# ultra-violet-tooth-sensor-mk-3_0.net
KiCad netlist of a schematic drawn in EAGLE
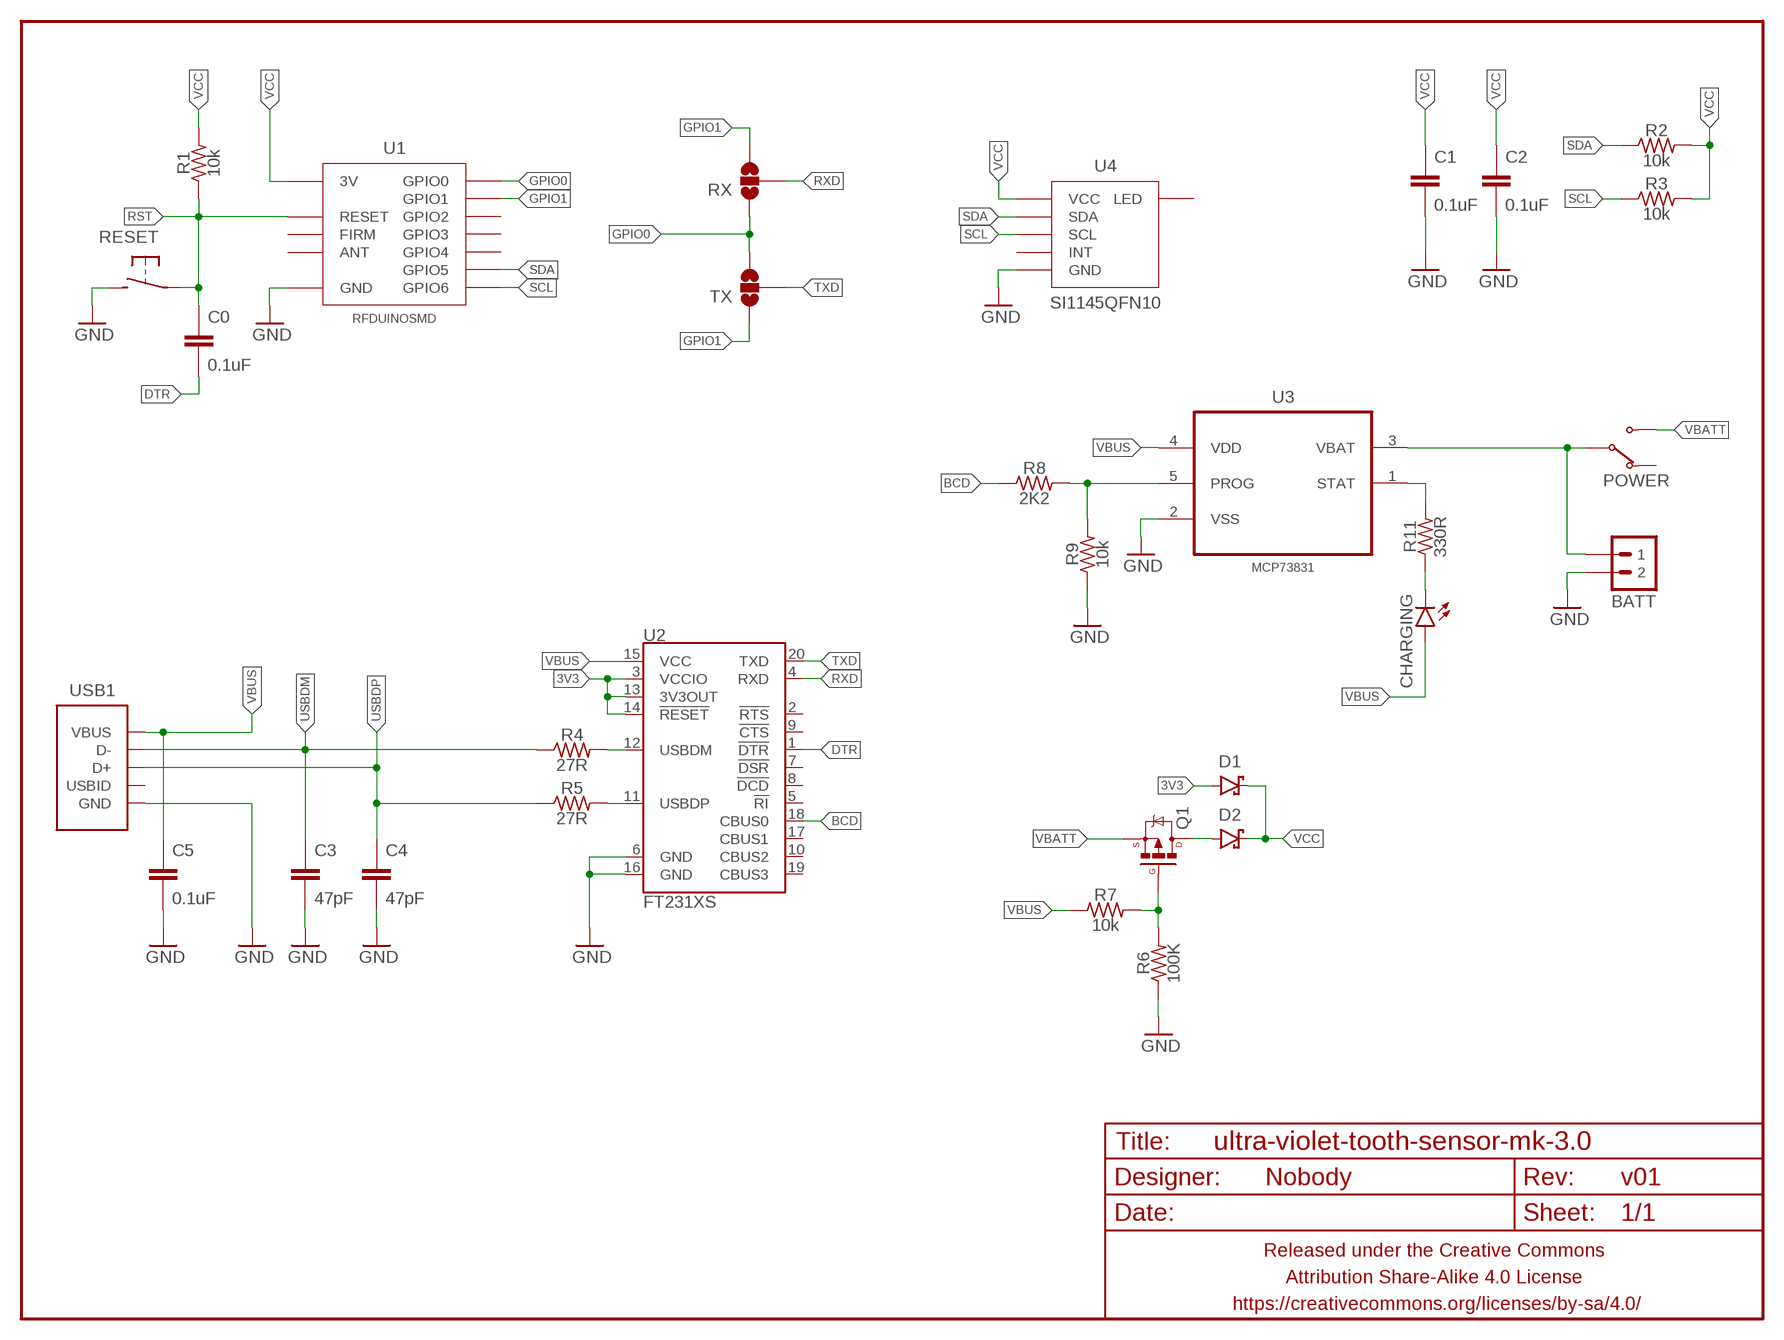
[diagram p0: schematic, sheet 1]

(export (version "E")
  (design (tool "Eeschema 10.0.6"))
  (components
    (comp (ref "BATT")
      (value "M02JST-2MM-SMT")
      (footprint "eagle-import:JST-2-SMD")
      (libsource (lib "eagle-import") (part "M02JST-2MM-SMT"))
    )
    (comp (ref "C0")
      (value "0.1uF")
      (footprint "eagle-import:C0603")
      (libsource (lib "eagle-import") (part "CAPACITOR-CERAMICC0603"))
    )
    (comp (ref "C1")
      (value "0.1uF")
      (footprint "eagle-import:C0603")
      (libsource (lib "eagle-import") (part "CAPACITOR-CERAMICC0603"))
    )
    (comp (ref "C2")
      (value "0.1uF")
      (footprint "eagle-import:C0603")
      (libsource (lib "eagle-import") (part "CAPACITOR-CERAMICC0603"))
    )
    (comp (ref "C3")
      (value "47pF")
      (footprint "eagle-import:C0603")
      (libsource (lib "eagle-import") (part "CAPACITOR-CERAMICC0603"))
    )
    (comp (ref "C4")
      (value "47pF")
      (footprint "eagle-import:C0603")
      (libsource (lib "eagle-import") (part "CAPACITOR-CERAMICC0603"))
    )
    (comp (ref "C5")
      (value "0.1uF")
      (footprint "eagle-import:C0603")
      (libsource (lib "eagle-import") (part "CAPACITOR-CERAMICC0603"))
    )
    (comp (ref "CHARGING")
      (value "LED1206")
      (footprint "eagle-import:LED-1206")
      (libsource (lib "eagle-import") (part "LED1206"))
    )
    (comp (ref "D1")
      (value "DIODE-SCHOTTKYSMA")
      (footprint "eagle-import:SMA-DIODE-SCHOTTKY")
      (libsource (lib "eagle-import") (part "DIODE-SCHOTTKYSMA"))
    )
    (comp (ref "D2")
      (value "DIODE-SCHOTTKYSMA")
      (footprint "eagle-import:SMA-DIODE-SCHOTTKY")
      (libsource (lib "eagle-import") (part "DIODE-SCHOTTKYSMA"))
    )
    (comp (ref "FRAME1")
      (value "FRAME-LETTERNO_PACKAGE")
      (footprint "eagle-import:DUMMY")
      (fields (field (name "DESIGNER") "Nobody"))
      (libsource (lib "eagle-import") (part "FRAME-LETTERNO_PACKAGE"))
    )
    (comp (ref "POWER")
      (value "SWITCH-SPDTPTH-RA-2.54MM")
      (footprint "eagle-import:SPDT-RA-2.54MM")
      (libsource (lib "eagle-import") (part "SWITCH-SPDTPTH-RA-2.54MM"))
    )
    (comp (ref "Q1")
      (value "MOSFET-PCHANNELIRLML2244")
      (footprint "eagle-import:SOT23-3")
      (libsource (lib "eagle-import") (part "MOSFET-PCHANNELIRLML2244"))
    )
    (comp (ref "R1")
      (value "10k")
      (footprint "eagle-import:R0603")
      (libsource (lib "eagle-import") (part "RESISTORR0603"))
    )
    (comp (ref "R2")
      (value "10k")
      (footprint "eagle-import:R0603")
      (libsource (lib "eagle-import") (part "RESISTORR0603"))
    )
    (comp (ref "R3")
      (value "10k")
      (footprint "eagle-import:R0603")
      (libsource (lib "eagle-import") (part "RESISTORR0603"))
    )
    (comp (ref "R4")
      (value "27R")
      (footprint "eagle-import:R0603")
      (libsource (lib "eagle-import") (part "RESISTORR0603"))
    )
    (comp (ref "R5")
      (value "27R")
      (footprint "eagle-import:R0603")
      (libsource (lib "eagle-import") (part "RESISTORR0603"))
    )
    (comp (ref "R6")
      (value "100K")
      (footprint "eagle-import:R0603")
      (libsource (lib "eagle-import") (part "RESISTORR0603"))
    )
    (comp (ref "R7")
      (value "10k")
      (footprint "eagle-import:R0603")
      (libsource (lib "eagle-import") (part "RESISTORR0603"))
    )
    (comp (ref "R8")
      (value "2K2")
      (footprint "eagle-import:R0603")
      (libsource (lib "eagle-import") (part "RESISTORR0603"))
    )
    (comp (ref "R9")
      (value "10k")
      (footprint "eagle-import:R0603")
      (libsource (lib "eagle-import") (part "RESISTORR0603"))
    )
    (comp (ref "R11")
      (value "330R")
      (footprint "eagle-import:R0603")
      (libsource (lib "eagle-import") (part "RESISTORR0603"))
    )
    (comp (ref "RESET")
      (value "SPST-NO-TACT3MM-RA")
      (footprint "eagle-import:TACTILE-PTH-SIDE")
      (libsource (lib "eagle-import") (part "SPST-NO-TACT3MM-RA"))
    )
    (comp (ref "RX")
      (value "JUMPER-PAD-3-NOFULL_BOX_SILK")
      (footprint "eagle-import:PAD-JUMPER-3-NO_YES_SILK_FULL_BOX")
      (libsource (lib "eagle-import") (part "JUMPER-PAD-3-NOFULL_BOX_SILK"))
    )
    (comp (ref "TX")
      (value "JUMPER-PAD-3-NOFULL_BOX_SILK")
      (footprint "eagle-import:PAD-JUMPER-3-NO_YES_SILK_FULL_BOX")
      (libsource (lib "eagle-import") (part "JUMPER-PAD-3-NOFULL_BOX_SILK"))
    )
    (comp (ref "U1")
      (value "RFDUINOSMD")
      (footprint "eagle-import:RFDUINO-SMD")
      (libsource (lib "eagle-import") (part "RFDUINOSMD"))
    )
    (comp (ref "U2")
      (value "FT231XS")
      (footprint "eagle-import:SSOP20_L")
      (libsource (lib "eagle-import") (part "FT231XS"))
    )
    (comp (ref "U3")
      (value "MCP73831")
      (footprint "eagle-import:SOT95P280X145-5N")
      (fields (field (name "MPN") "MCP73831T-2ACI/OT"))
      (libsource (lib "eagle-import") (part "MCP73831T-2ACI/OT"))
    )
    (comp (ref "U4")
      (value "SI1145QFN10")
      (footprint "eagle-import:SI1145")
      (libsource (lib "eagle-import") (part "SI1145QFN10"))
    )
    (comp (ref "USB1")
      (value "USB-ABCOMBO")
      (footprint "eagle-import:USB-MICRO-B-FCI-CUTOUT")
      (libsource (lib "eagle-import") (part "USB-ABCOMBO"))
    )
  )
  (nets
    (net (code "1") (name "3V3") (class "Default")
      (node (ref "D1") (pin "A") (pinfunction "A_A") (pintype "passive"))
      (node (ref "U2") (pin "13") (pinfunction "3V3OUT_13") (pintype "bidirectional"))
      (node (ref "U2") (pin "14") (pinfunction "~{RESET}_14") (pintype "bidirectional"))
      (node (ref "U2") (pin "3") (pinfunction "VCCIO_3") (pintype "bidirectional"))
    )
    (net (code "2") (name "BCD") (class "Default")
      (node (ref "R8") (pin "1") (pinfunction "1_1") (pintype "passive"))
      (node (ref "U2") (pin "18") (pinfunction "CBUS0_18") (pintype "bidirectional"))
    )
    (net (code "3") (name "DTR") (class "Default")
      (node (ref "C0") (pin "2") (pinfunction "2_2") (pintype "passive"))
      (node (ref "U2") (pin "1") (pinfunction "~{DTR}_1") (pintype "bidirectional"))
    )
    (net (code "4") (name "GND") (class "Default")
      (node (ref "BATT") (pin "1") (pinfunction "2_1") (pintype "passive"))
      (node (ref "C1") (pin "2") (pinfunction "2_2") (pintype "passive"))
      (node (ref "C2") (pin "2") (pinfunction "2_2") (pintype "passive"))
      (node (ref "C3") (pin "2") (pinfunction "2_2") (pintype "passive"))
      (node (ref "C4") (pin "2") (pinfunction "2_2") (pintype "passive"))
      (node (ref "C5") (pin "2") (pinfunction "2_2") (pintype "passive"))
      (node (ref "R6") (pin "1") (pinfunction "1_1") (pintype "passive"))
      (node (ref "R9") (pin "1") (pinfunction "1_1") (pintype "passive"))
      (node (ref "RESET") (pin "2") (pinfunction "2_2") (pintype "passive"))
      (node (ref "U1") (pin "GND@1") (pinfunction "GND_GND@1") (pintype "bidirectional"))
      (node (ref "U1") (pin "GND@2") (pinfunction "GND_GND@2") (pintype "bidirectional"))
      (node (ref "U1") (pin "GND@3") (pinfunction "GND_GND@3") (pintype "bidirectional"))
      (node (ref "U1") (pin "GND@4") (pinfunction "GND_GND@4") (pintype "bidirectional"))
      (node (ref "U1") (pin "GND@5") (pinfunction "GND_GND@5") (pintype "bidirectional"))
      (node (ref "U1") (pin "GND@6") (pinfunction "GND_GND@6") (pintype "bidirectional"))
      (node (ref "U1") (pin "GND@7") (pinfunction "GND_GND@7") (pintype "bidirectional"))
      (node (ref "U1") (pin "GND@8") (pinfunction "GND_GND@8") (pintype "bidirectional"))
      (node (ref "U2") (pin "16") (pinfunction "GND_16") (pintype "bidirectional"))
      (node (ref "U2") (pin "6") (pinfunction "GND_6") (pintype "bidirectional"))
      (node (ref "U3") (pin "2") (pinfunction "VSS_2") (pintype "power_in"))
      (node (ref "U4") (pin "GND") (pinfunction "GND_GND") (pintype "bidirectional"))
      (node (ref "USB1") (pin "5") (pinfunction "GND_5") (pintype "bidirectional"))
      (node (ref "USB1") (pin "P$1") (pinfunction "GND_P$1") (pintype "bidirectional"))
      (node (ref "USB1") (pin "P$2") (pinfunction "GND_P$2") (pintype "bidirectional"))
    )
    (net (code "5") (name "GPIO0") (class "Default")
      (node (ref "RX") (pin "1") (pinfunction "1_1") (pintype "passive"))
      (node (ref "TX") (pin "3") (pinfunction "3_3") (pintype "passive"))
      (node (ref "U1") (pin "GPIO0") (pinfunction "GPIO0_GPIO0") (pintype "bidirectional"))
    )
    (net (code "6") (name "GPIO1") (class "Default")
      (node (ref "RX") (pin "3") (pinfunction "3_3") (pintype "passive"))
      (node (ref "TX") (pin "1") (pinfunction "1_1") (pintype "passive"))
      (node (ref "U1") (pin "GPIO1") (pinfunction "GPIO1_GPIO1") (pintype "bidirectional"))
    )
    (net (code "7") (name "Net-(BATT-1)") (class "Default")
      (node (ref "BATT") (pin "2") (pinfunction "1_2") (pintype "passive"))
      (node (ref "POWER") (pin "2") (pinfunction "COM_2") (pintype "passive"))
      (node (ref "U3") (pin "3") (pinfunction "VBAT_3") (pintype "output"))
    )
    (net (code "8") (name "Net-(CHARGING-PadC)") (class "Default")
      (node (ref "CHARGING") (pin "C") (pinfunction "C_C") (pintype "passive"))
      (node (ref "R11") (pin "1") (pinfunction "1_1") (pintype "passive"))
    )
    (net (code "9") (name "Net-(Q1-D)") (class "Default")
      (node (ref "D2") (pin "A") (pinfunction "A_A") (pintype "passive"))
      (node (ref "Q1") (pin "3") (pinfunction "D_3") (pintype "passive"))
    )
    (net (code "10") (name "Net-(Q1-G)") (class "Default")
      (node (ref "Q1") (pin "1") (pinfunction "G_1") (pintype "passive"))
      (node (ref "R6") (pin "2") (pinfunction "2_2") (pintype "passive"))
      (node (ref "R7") (pin "2") (pinfunction "2_2") (pintype "passive"))
    )
    (net (code "11") (name "Net-(U2-USBDM)") (class "Default")
      (node (ref "R4") (pin "2") (pinfunction "2_2") (pintype "passive"))
      (node (ref "U2") (pin "12") (pinfunction "USBDM_12") (pintype "bidirectional"))
    )
    (net (code "12") (name "Net-(U2-USBDP)") (class "Default")
      (node (ref "R5") (pin "2") (pinfunction "2_2") (pintype "passive"))
      (node (ref "U2") (pin "11") (pinfunction "USBDP_11") (pintype "bidirectional"))
    )
    (net (code "13") (name "Net-(U3-PROG)") (class "Default")
      (node (ref "R8") (pin "2") (pinfunction "2_2") (pintype "passive"))
      (node (ref "R9") (pin "2") (pinfunction "2_2") (pintype "passive"))
      (node (ref "U3") (pin "5") (pinfunction "PROG_5") (pintype "input"))
    )
    (net (code "14") (name "Net-(U3-STAT)") (class "Default")
      (node (ref "R11") (pin "2") (pinfunction "2_2") (pintype "passive"))
      (node (ref "U3") (pin "1") (pinfunction "STAT_1") (pintype "output"))
    )
    (net (code "15") (name "RST") (class "Default")
      (node (ref "C0") (pin "1") (pinfunction "1_1") (pintype "passive"))
      (node (ref "R1") (pin "1") (pinfunction "1_1") (pintype "passive"))
      (node (ref "RESET") (pin "1") (pinfunction "1_1") (pintype "passive"))
      (node (ref "U1") (pin "RESET") (pinfunction "RESET_RESET") (pintype "bidirectional"))
    )
    (net (code "16") (name "RXD") (class "Default")
      (node (ref "RX") (pin "2") (pinfunction "2_2") (pintype "passive"))
      (node (ref "U2") (pin "4") (pinfunction "RXD_4") (pintype "bidirectional"))
    )
    (net (code "17") (name "SCL") (class "Default")
      (node (ref "R3") (pin "1") (pinfunction "1_1") (pintype "passive"))
      (node (ref "U1") (pin "GPIO6") (pinfunction "GPIO6_GPIO6") (pintype "bidirectional"))
      (node (ref "U4") (pin "SCL") (pinfunction "SCL_SCL") (pintype "bidirectional"))
    )
    (net (code "18") (name "SDA") (class "Default")
      (node (ref "R2") (pin "1") (pinfunction "1_1") (pintype "passive"))
      (node (ref "U1") (pin "GPIO5") (pinfunction "GPIO5_GPIO5") (pintype "bidirectional"))
      (node (ref "U4") (pin "SDA") (pinfunction "SDA_SDA") (pintype "bidirectional"))
    )
    (net (code "19") (name "TXD") (class "Default")
      (node (ref "TX") (pin "2") (pinfunction "2_2") (pintype "passive"))
      (node (ref "U2") (pin "20") (pinfunction "TXD_20") (pintype "bidirectional"))
    )
    (net (code "20") (name "USBDM") (class "Default")
      (node (ref "C3") (pin "1") (pinfunction "1_1") (pintype "passive"))
      (node (ref "R4") (pin "1") (pinfunction "1_1") (pintype "passive"))
      (node (ref "USB1") (pin "2") (pinfunction "D-_2") (pintype "bidirectional"))
    )
    (net (code "21") (name "USBDP") (class "Default")
      (node (ref "C4") (pin "1") (pinfunction "1_1") (pintype "passive"))
      (node (ref "R5") (pin "1") (pinfunction "1_1") (pintype "passive"))
      (node (ref "USB1") (pin "3") (pinfunction "D+_3") (pintype "bidirectional"))
    )
    (net (code "22") (name "VBATT") (class "Default")
      (node (ref "POWER") (pin "3") (pinfunction "NO_3") (pintype "passive"))
      (node (ref "Q1") (pin "2") (pinfunction "S_2") (pintype "passive"))
    )
    (net (code "23") (name "VBUS") (class "Default")
      (node (ref "C5") (pin "1") (pinfunction "1_1") (pintype "passive"))
      (node (ref "CHARGING") (pin "A") (pinfunction "A_A") (pintype "passive"))
      (node (ref "R7") (pin "1") (pinfunction "1_1") (pintype "passive"))
      (node (ref "U2") (pin "15") (pinfunction "VCC_15") (pintype "bidirectional"))
      (node (ref "U3") (pin "4") (pinfunction "VDD_4") (pintype "power_in"))
      (node (ref "USB1") (pin "1") (pinfunction "VBUS_1") (pintype "bidirectional"))
    )
    (net (code "24") (name "VCC") (class "Default")
      (node (ref "C1") (pin "1") (pinfunction "1_1") (pintype "passive"))
      (node (ref "C2") (pin "1") (pinfunction "1_1") (pintype "passive"))
      (node (ref "D1") (pin "C") (pinfunction "C_C") (pintype "passive"))
      (node (ref "D2") (pin "C") (pinfunction "C_C") (pintype "passive"))
      (node (ref "R1") (pin "2") (pinfunction "2_2") (pintype "passive"))
      (node (ref "R2") (pin "2") (pinfunction "2_2") (pintype "passive"))
      (node (ref "R3") (pin "2") (pinfunction "2_2") (pintype "passive"))
      (node (ref "U1") (pin "3V") (pinfunction "3V_3V") (pintype "bidirectional"))
      (node (ref "U4") (pin "VCC@1") (pinfunction "VCC_VCC@1") (pintype "bidirectional"))
      (node (ref "U4") (pin "VCC@2") (pinfunction "VCC_VCC@2") (pintype "bidirectional"))
      (node (ref "U4") (pin "VCC@3") (pinfunction "VCC_VCC@3") (pintype "bidirectional"))
    )
    (net (code "25") (name "unconnected-(POWER-NC-Pad1)") (class "Default")
      (node (ref "POWER") (pin "1") (pinfunction "NC_1") (pintype "passive"))
    )
    (net (code "26") (name "unconnected-(U1-FIRM-PadFACTORY)") (class "Default")
      (node (ref "U1") (pin "FACTORY") (pinfunction "FIRM_FACTORY") (pintype "bidirectional"))
    )
    (net (code "27") (name "unconnected-(U1-PadANT)") (class "Default")
      (node (ref "U1") (pin "ANT") (pinfunction "ANT_ANT") (pintype "bidirectional"))
    )
    (net (code "28") (name "unconnected-(U1-PadGPIO2)") (class "Default")
      (node (ref "U1") (pin "GPIO2") (pinfunction "GPIO2_GPIO2") (pintype "bidirectional"))
    )
    (net (code "29") (name "unconnected-(U1-PadGPIO3)") (class "Default")
      (node (ref "U1") (pin "GPIO3") (pinfunction "GPIO3_GPIO3") (pintype "bidirectional"))
    )
    (net (code "30") (name "unconnected-(U1-PadGPIO4)") (class "Default")
      (node (ref "U1") (pin "GPIO4") (pinfunction "GPIO4_GPIO4") (pintype "bidirectional"))
    )
    (net (code "31") (name "unconnected-(U2-CBUS1-Pad17)") (class "Default")
      (node (ref "U2") (pin "17") (pinfunction "CBUS1_17") (pintype "bidirectional"))
    )
    (net (code "32") (name "unconnected-(U2-CBUS2-Pad10)") (class "Default")
      (node (ref "U2") (pin "10") (pinfunction "CBUS2_10") (pintype "bidirectional"))
    )
    (net (code "33") (name "unconnected-(U2-CBUS3-Pad19)") (class "Default")
      (node (ref "U2") (pin "19") (pinfunction "CBUS3_19") (pintype "bidirectional"))
    )
    (net (code "34") (name "unconnected-(U2-~{CTS}-Pad9)") (class "Default")
      (node (ref "U2") (pin "9") (pinfunction "~{CTS}_9") (pintype "bidirectional"))
    )
    (net (code "35") (name "unconnected-(U2-~{DCD}-Pad8)") (class "Default")
      (node (ref "U2") (pin "8") (pinfunction "~{DCD}_8") (pintype "bidirectional"))
    )
    (net (code "36") (name "unconnected-(U2-~{DSR}-Pad7)") (class "Default")
      (node (ref "U2") (pin "7") (pinfunction "~{DSR}_7") (pintype "bidirectional"))
    )
    (net (code "37") (name "unconnected-(U2-~{RI}-Pad5)") (class "Default")
      (node (ref "U2") (pin "5") (pinfunction "~{RI}_5") (pintype "bidirectional"))
    )
    (net (code "38") (name "unconnected-(U2-~{RTS}-Pad2)") (class "Default")
      (node (ref "U2") (pin "2") (pinfunction "~{RTS}_2") (pintype "bidirectional"))
    )
    (net (code "39") (name "unconnected-(U4-PadINT)") (class "Default")
      (node (ref "U4") (pin "INT") (pinfunction "INT_INT") (pintype "bidirectional"))
    )
    (net (code "40") (name "unconnected-(U4-PadLED)") (class "Default")
      (node (ref "U4") (pin "LED") (pinfunction "LED_LED") (pintype "bidirectional"))
    )
    (net (code "41") (name "unconnected-(USB1-USBID-Pad4)") (class "Default")
      (node (ref "USB1") (pin "4") (pinfunction "USBID_4") (pintype "bidirectional"))
    )
  )
)
